# 02_Beam_Inputs.net
KiCad netlist of a schematic drawn in Altium Designer
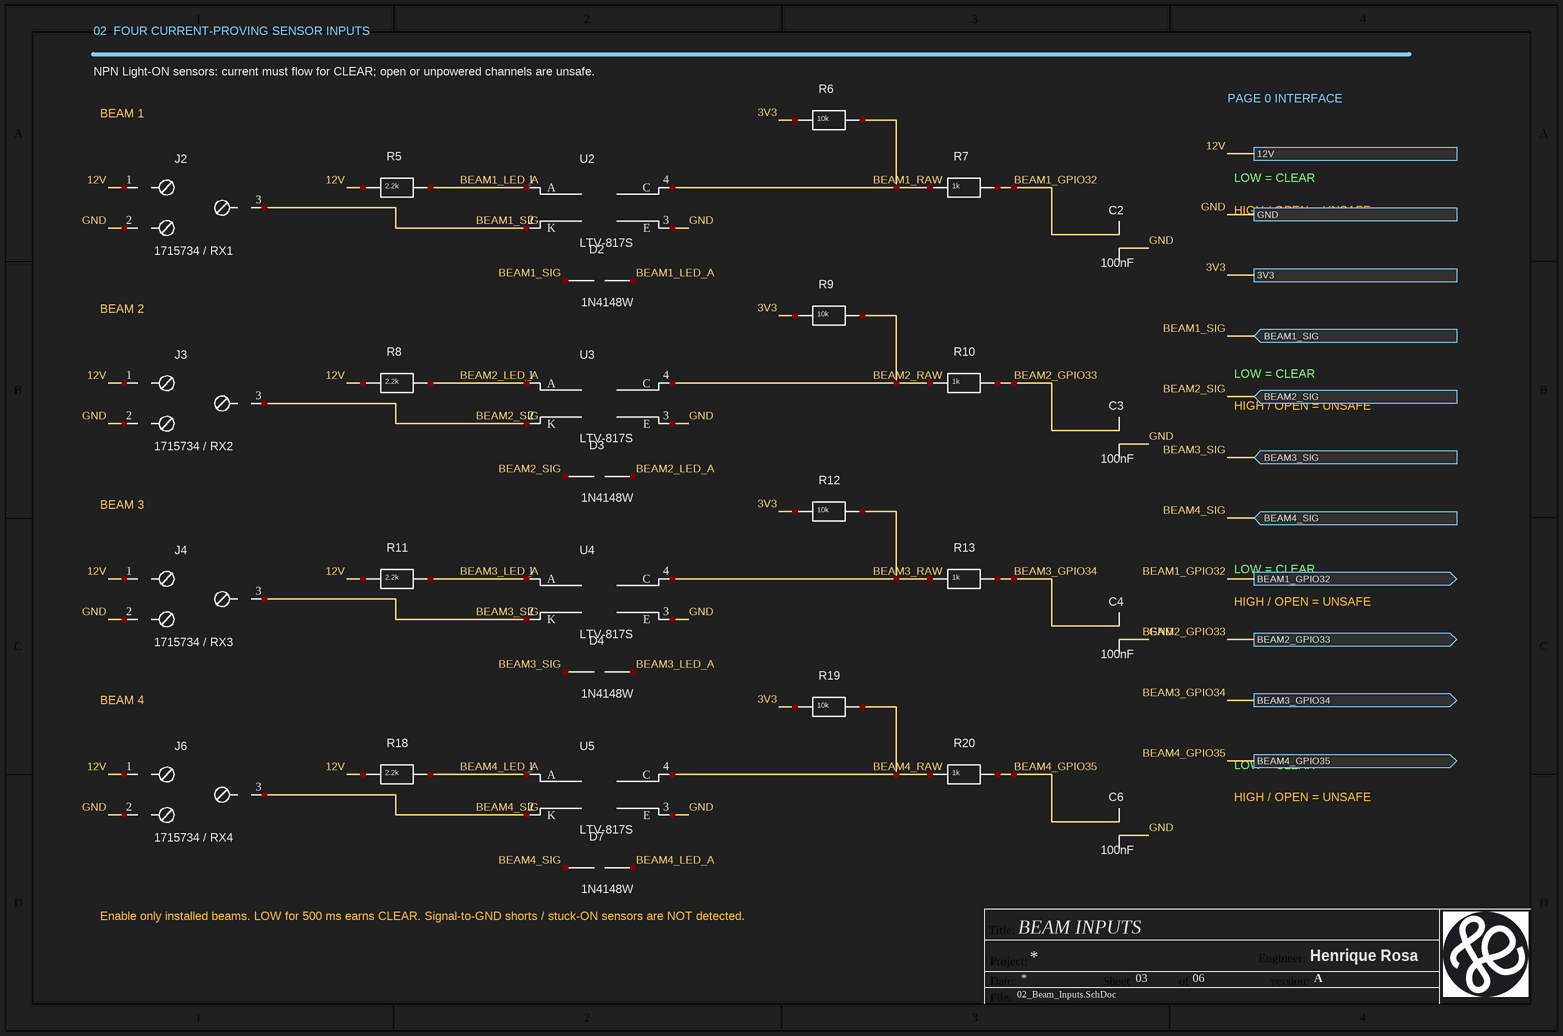
[diagram p0: 02_Beam_Inputs.SchDoc]

(export (version "E")
  (design (tool "Eeschema 10.0.6"))
  (components
    (comp (ref "C2")
      (value "100nF")
      (footprint "PCB - CAPACITOR - MLCC - MURATA GRM21B 0805_2012:MURATA GRM21B 0805_2012")
      (description "Input RC filter")
      (fields (field (name "PART NUMBER") "GRM21BR71H104KA01L") (field (name "MANUFACTURER") "Murata"))
      (libsource (lib "ReviewedComponents_20260912-233454") (part "GRM21BR71H104KA01L__C2_view"))
    )
    (comp (ref "C3")
      (value "100nF")
      (footprint "PCB - CAPACITOR - MLCC - MURATA GRM21B 0805_2012:MURATA GRM21B 0805_2012")
      (description "Input RC filter")
      (fields (field (name "PART NUMBER") "GRM21BR71H104KA01L") (field (name "MANUFACTURER") "Murata"))
      (libsource (lib "ReviewedComponents_20260912-233454") (part "GRM21BR71H104KA01L__C3_view"))
    )
    (comp (ref "C4")
      (value "100nF")
      (footprint "PCB - CAPACITOR - MLCC - MURATA GRM21B 0805_2012:MURATA GRM21B 0805_2012")
      (description "Input RC filter")
      (fields (field (name "PART NUMBER") "GRM21BR71H104KA01L") (field (name "MANUFACTURER") "Murata"))
      (libsource (lib "ReviewedComponents_20260912-233454") (part "GRM21BR71H104KA01L__C4_view"))
    )
    (comp (ref "C6")
      (value "100nF")
      (footprint "PCB - CAPACITOR - MLCC - MURATA GRM21B 0805_2012:MURATA GRM21B 0805_2012")
      (description "Input RC filter")
      (fields (field (name "PART NUMBER") "GRM21BR71H104KA01L") (field (name "MANUFACTURER") "Murata"))
      (libsource (lib "ReviewedComponents_20260912-233454") (part "GRM21BR71H104KA01L__C6_view"))
    )
    (comp (ref "D2")
      (value "1N4148W")
      (footprint "PinRepairFootprints:1N4148W_SOD123_A1_K2")
      (description "Reverse clamp: A to SIG; K to opto LED anode")
      (fields (field (name "MANUFACTURER") "Nexperia"))
      (libsource (lib "ReviewedComponents_20260912-233454") (part "1N4148W__D2_view"))
    )
    (comp (ref "D3")
      (value "1N4148W")
      (footprint "PinRepairFootprints:1N4148W_SOD123_A1_K2")
      (description "Reverse clamp: A to SIG; K to opto LED anode")
      (fields (field (name "MANUFACTURER") "Nexperia"))
      (libsource (lib "ReviewedComponents_20260912-233454") (part "1N4148W__D3_view"))
    )
    (comp (ref "D4")
      (value "1N4148W")
      (footprint "PinRepairFootprints:1N4148W_SOD123_A1_K2")
      (description "Reverse clamp: A to SIG; K to opto LED anode")
      (fields (field (name "MANUFACTURER") "Nexperia"))
      (libsource (lib "ReviewedComponents_20260912-233454") (part "1N4148W__D4_view"))
    )
    (comp (ref "D7")
      (value "1N4148W")
      (footprint "PinRepairFootprints:1N4148W_SOD123_A1_K2")
      (description "Reverse clamp: A to SIG; K to opto LED anode")
      (fields (field (name "MANUFACTURER") "Nexperia"))
      (libsource (lib "ReviewedComponents_20260912-233454") (part "1N4148W__D7_view"))
    )
    (comp (ref "J2")
      (value "1715734 / RX1")
      (footprint "OpticalHardware:PHOENIX_1715734_MKDS_3_508")
      (description "12V / GND / NPN signal terminal")
      (fields
        (field (name "MANUFACTURER") "Phoenix Contact")
        (field (name "MANUFACTURER PART NUMBER") "1715734")
      )
      (libsource (lib "ReviewedComponents_20260912-233454") (part "1715734__J2_view"))
    )
    (comp (ref "J3")
      (value "1715734 / RX2")
      (footprint "OpticalHardware:PHOENIX_1715734_MKDS_3_508")
      (description "12V / GND / NPN signal terminal")
      (fields
        (field (name "MANUFACTURER") "Phoenix Contact")
        (field (name "MANUFACTURER PART NUMBER") "1715734")
      )
      (libsource (lib "ReviewedComponents_20260912-233454") (part "1715734__J3_view"))
    )
    (comp (ref "J4")
      (value "1715734 / RX3")
      (footprint "OpticalHardware:PHOENIX_1715734_MKDS_3_508")
      (description "12V / GND / NPN signal terminal")
      (fields
        (field (name "MANUFACTURER") "Phoenix Contact")
        (field (name "MANUFACTURER PART NUMBER") "1715734")
      )
      (libsource (lib "ReviewedComponents_20260912-233454") (part "1715734__J4_view"))
    )
    (comp (ref "J6")
      (value "1715734 / RX4")
      (footprint "OpticalHardware:PHOENIX_1715734_MKDS_3_508")
      (description "12V / GND / NPN signal terminal")
      (fields
        (field (name "MANUFACTURER") "Phoenix Contact")
        (field (name "MANUFACTURER PART NUMBER") "1715734")
      )
      (libsource (lib "ReviewedComponents_20260912-233454") (part "1715734__J6_view"))
    )
    (comp (ref "R5")
      (value "2.2k")
      (footprint "PCB - RESISTOR - CHIP - YAGEO RES 0805_2012:YAGEO RES 0805_2012")
      (description "Optocoupler LED current limit")
      (fields (field (name "PART NUMBER") "RC0805FR-072K2L") (field (name "MANUFACTURER") "Yageo"))
      (libsource (lib "ReviewedComponents_20260912-233454") (part "RC0805FR-072K2L__R5_view"))
    )
    (comp (ref "R6")
      (value "10k")
      (footprint "PCB - RESISTOR - CHIP - YAGEO RES 0805_2012:YAGEO RES 0805_2012")
      (description "Pull-up earns unsafe if optocoupler is off")
      (fields (field (name "PART NUMBER") "RC0805FR-0710KL") (field (name "MANUFACTURER") "Yageo"))
      (libsource (lib "ReviewedComponents_20260912-233454") (part "RC0805FR-0710KL__R6_view"))
    )
    (comp (ref "R7")
      (value "1k")
      (footprint "PCB - RESISTOR - CHIP - YAGEO RES 0805_2012:YAGEO RES 0805_2012")
      (description "Input current limit")
      (fields (field (name "PART NUMBER") "RC0805FR-071KL") (field (name "MANUFACTURER") "Yageo"))
      (libsource (lib "ReviewedComponents_20260912-233454") (part "RC0805FR-071KL__R7_view"))
    )
    (comp (ref "R8")
      (value "2.2k")
      (footprint "PCB - RESISTOR - CHIP - YAGEO RES 0805_2012:YAGEO RES 0805_2012")
      (description "Optocoupler LED current limit")
      (fields (field (name "PART NUMBER") "RC0805FR-072K2L") (field (name "MANUFACTURER") "Yageo"))
      (libsource (lib "ReviewedComponents_20260912-233454") (part "RC0805FR-072K2L__R8_view"))
    )
    (comp (ref "R9")
      (value "10k")
      (footprint "PCB - RESISTOR - CHIP - YAGEO RES 0805_2012:YAGEO RES 0805_2012")
      (description "Pull-up earns unsafe if optocoupler is off")
      (fields (field (name "PART NUMBER") "RC0805FR-0710KL") (field (name "MANUFACTURER") "Yageo"))
      (libsource (lib "ReviewedComponents_20260912-233454") (part "RC0805FR-0710KL__R9_view"))
    )
    (comp (ref "R10")
      (value "1k")
      (footprint "PCB - RESISTOR - CHIP - YAGEO RES 0805_2012:YAGEO RES 0805_2012")
      (description "Input current limit")
      (fields (field (name "PART NUMBER") "RC0805FR-071KL") (field (name "MANUFACTURER") "Yageo"))
      (libsource (lib "ReviewedComponents_20260912-233454") (part "RC0805FR-071KL__R10_view"))
    )
    (comp (ref "R11")
      (value "2.2k")
      (footprint "PCB - RESISTOR - CHIP - YAGEO RES 0805_2012:YAGEO RES 0805_2012")
      (description "Optocoupler LED current limit")
      (fields (field (name "PART NUMBER") "RC0805FR-072K2L") (field (name "MANUFACTURER") "Yageo"))
      (libsource (lib "ReviewedComponents_20260912-233454") (part "RC0805FR-072K2L__R11_view"))
    )
    (comp (ref "R12")
      (value "10k")
      (footprint "PCB - RESISTOR - CHIP - YAGEO RES 0805_2012:YAGEO RES 0805_2012")
      (description "Pull-up earns unsafe if optocoupler is off")
      (fields (field (name "PART NUMBER") "RC0805FR-0710KL") (field (name "MANUFACTURER") "Yageo"))
      (libsource (lib "ReviewedComponents_20260912-233454") (part "RC0805FR-0710KL__R12_view"))
    )
    (comp (ref "R13")
      (value "1k")
      (footprint "PCB - RESISTOR - CHIP - YAGEO RES 0805_2012:YAGEO RES 0805_2012")
      (description "Input current limit")
      (fields (field (name "PART NUMBER") "RC0805FR-071KL") (field (name "MANUFACTURER") "Yageo"))
      (libsource (lib "ReviewedComponents_20260912-233454") (part "RC0805FR-071KL__R13_view"))
    )
    (comp (ref "R18")
      (value "2.2k")
      (footprint "PCB - RESISTOR - CHIP - YAGEO RES 0805_2012:YAGEO RES 0805_2012")
      (description "Optocoupler LED current limit")
      (fields (field (name "PART NUMBER") "RC0805FR-072K2L") (field (name "MANUFACTURER") "Yageo"))
      (libsource (lib "ReviewedComponents_20260912-233454") (part "RC0805FR-072K2L__R18_view"))
    )
    (comp (ref "R19")
      (value "10k")
      (footprint "PCB - RESISTOR - CHIP - YAGEO RES 0805_2012:YAGEO RES 0805_2012")
      (description "Pull-up earns unsafe if optocoupler is off")
      (fields (field (name "PART NUMBER") "RC0805FR-0710KL") (field (name "MANUFACTURER") "Yageo"))
      (libsource (lib "ReviewedComponents_20260912-233454") (part "RC0805FR-0710KL__R19_view"))
    )
    (comp (ref "R20")
      (value "1k")
      (footprint "PCB - RESISTOR - CHIP - YAGEO RES 0805_2012:YAGEO RES 0805_2012")
      (description "Input current limit")
      (fields (field (name "PART NUMBER") "RC0805FR-071KL") (field (name "MANUFACTURER") "Yageo"))
      (libsource (lib "ReviewedComponents_20260912-233454") (part "RC0805FR-071KL__R20_view"))
    )
    (comp (ref "U2")
      (value "LTV-817S")
      (footprint "PCB - OPTOISOLATOR - LITEON LTV-817:LITEON LTV-817")
      (description "Phototransistor optocoupler")
      (fields
        (field (name "MANUFACTURER") "Lite-On")
        (field (name "MANUFACTURER PART NUMBER") "LTV-817S-TA1")
      )
      (libsource (lib "ReviewedComponents_20260912-233454") (part "LTV-817S-TA1__U2_view"))
    )
    (comp (ref "U3")
      (value "LTV-817S")
      (footprint "PCB - OPTOISOLATOR - LITEON LTV-817:LITEON LTV-817")
      (description "Phototransistor optocoupler")
      (fields
        (field (name "MANUFACTURER") "Lite-On")
        (field (name "MANUFACTURER PART NUMBER") "LTV-817S-TA1")
      )
      (libsource (lib "ReviewedComponents_20260912-233454") (part "LTV-817S-TA1__U3_view"))
    )
    (comp (ref "U4")
      (value "LTV-817S")
      (footprint "PCB - OPTOISOLATOR - LITEON LTV-817:LITEON LTV-817")
      (description "Phototransistor optocoupler")
      (fields
        (field (name "MANUFACTURER") "Lite-On")
        (field (name "MANUFACTURER PART NUMBER") "LTV-817S-TA1")
      )
      (libsource (lib "ReviewedComponents_20260912-233454") (part "LTV-817S-TA1__U4_view"))
    )
    (comp (ref "U5")
      (value "LTV-817S")
      (footprint "PCB - OPTOISOLATOR - LITEON LTV-817:LITEON LTV-817")
      (description "Phototransistor optocoupler")
      (fields
        (field (name "MANUFACTURER") "Lite-On")
        (field (name "MANUFACTURER PART NUMBER") "LTV-817S-TA1")
      )
      (libsource (lib "ReviewedComponents_20260912-233454") (part "LTV-817S-TA1__U5_view"))
    )
  )
  (nets
    (net (code "1") (name "/3V3") (class "Default")
      (node (ref "R12") (pin "1") (pinfunction "1_1") (pintype "passive"))
      (node (ref "R19") (pin "1") (pinfunction "1_1") (pintype "passive"))
      (node (ref "R6") (pin "1") (pinfunction "1_1") (pintype "passive"))
      (node (ref "R9") (pin "1") (pinfunction "1_1") (pintype "passive"))
    )
    (net (code "2") (name "/12V") (class "Default")
      (node (ref "J2") (pin "1") (pinfunction "+12V_1") (pintype "passive"))
      (node (ref "J3") (pin "1") (pinfunction "+12V_1") (pintype "passive"))
      (node (ref "J4") (pin "1") (pinfunction "+12V_1") (pintype "passive"))
      (node (ref "J6") (pin "1") (pinfunction "+12V_1") (pintype "passive"))
      (node (ref "R11") (pin "1") (pinfunction "1_1") (pintype "passive"))
      (node (ref "R18") (pin "1") (pinfunction "1_1") (pintype "passive"))
      (node (ref "R5") (pin "1") (pinfunction "1_1") (pintype "passive"))
      (node (ref "R8") (pin "1") (pinfunction "1_1") (pintype "passive"))
    )
    (net (code "3") (name "/BEAM1_GPIO32") (class "Default")
      (node (ref "R7") (pin "2") (pinfunction "2_2") (pintype "passive"))
    )
    (net (code "4") (name "/BEAM1_LED_A") (class "Default")
      (node (ref "D2") (pin "2") (pinfunction "K_2") (pintype "passive"))
      (node (ref "R5") (pin "2") (pinfunction "2_2") (pintype "passive"))
      (node (ref "U2") (pin "1") (pinfunction "A_1") (pintype "passive"))
    )
    (net (code "5") (name "/BEAM1_RAW") (class "Default")
      (node (ref "R6") (pin "2") (pinfunction "2_2") (pintype "passive"))
      (node (ref "R7") (pin "1") (pinfunction "1_1") (pintype "passive"))
      (node (ref "U2") (pin "4") (pinfunction "C_4") (pintype "open_collector"))
    )
    (net (code "6") (name "/BEAM1_SIG") (class "Default")
      (node (ref "D2") (pin "1") (pinfunction "A_1") (pintype "passive"))
      (node (ref "J2") (pin "3") (pinfunction "OUT_3") (pintype "passive"))
      (node (ref "U2") (pin "2") (pinfunction "K_2") (pintype "passive"))
    )
    (net (code "7") (name "/BEAM2_GPIO33") (class "Default")
      (node (ref "R10") (pin "2") (pinfunction "2_2") (pintype "passive"))
    )
    (net (code "8") (name "/BEAM2_LED_A") (class "Default")
      (node (ref "D3") (pin "2") (pinfunction "K_2") (pintype "passive"))
      (node (ref "R8") (pin "2") (pinfunction "2_2") (pintype "passive"))
      (node (ref "U3") (pin "1") (pinfunction "A_1") (pintype "passive"))
    )
    (net (code "9") (name "/BEAM2_RAW") (class "Default")
      (node (ref "R10") (pin "1") (pinfunction "1_1") (pintype "passive"))
      (node (ref "R9") (pin "2") (pinfunction "2_2") (pintype "passive"))
      (node (ref "U3") (pin "4") (pinfunction "C_4") (pintype "open_collector"))
    )
    (net (code "10") (name "/BEAM2_SIG") (class "Default")
      (node (ref "D3") (pin "1") (pinfunction "A_1") (pintype "passive"))
      (node (ref "J3") (pin "3") (pinfunction "OUT_3") (pintype "passive"))
      (node (ref "U3") (pin "2") (pinfunction "K_2") (pintype "passive"))
    )
    (net (code "11") (name "/BEAM3_GPIO34") (class "Default")
      (node (ref "R13") (pin "2") (pinfunction "2_2") (pintype "passive"))
    )
    (net (code "12") (name "/BEAM3_LED_A") (class "Default")
      (node (ref "D4") (pin "2") (pinfunction "K_2") (pintype "passive"))
      (node (ref "R11") (pin "2") (pinfunction "2_2") (pintype "passive"))
      (node (ref "U4") (pin "1") (pinfunction "A_1") (pintype "passive"))
    )
    (net (code "13") (name "/BEAM3_RAW") (class "Default")
      (node (ref "R12") (pin "2") (pinfunction "2_2") (pintype "passive"))
      (node (ref "R13") (pin "1") (pinfunction "1_1") (pintype "passive"))
      (node (ref "U4") (pin "4") (pinfunction "C_4") (pintype "open_collector"))
    )
    (net (code "14") (name "/BEAM3_SIG") (class "Default")
      (node (ref "D4") (pin "1") (pinfunction "A_1") (pintype "passive"))
      (node (ref "J4") (pin "3") (pinfunction "OUT_3") (pintype "passive"))
      (node (ref "U4") (pin "2") (pinfunction "K_2") (pintype "passive"))
    )
    (net (code "15") (name "/BEAM4_GPIO35") (class "Default")
      (node (ref "R20") (pin "2") (pinfunction "2_2") (pintype "passive"))
    )
    (net (code "16") (name "/BEAM4_LED_A") (class "Default")
      (node (ref "D7") (pin "2") (pinfunction "K_2") (pintype "passive"))
      (node (ref "R18") (pin "2") (pinfunction "2_2") (pintype "passive"))
      (node (ref "U5") (pin "1") (pinfunction "A_1") (pintype "passive"))
    )
    (net (code "17") (name "/BEAM4_RAW") (class "Default")
      (node (ref "R19") (pin "2") (pinfunction "2_2") (pintype "passive"))
      (node (ref "R20") (pin "1") (pinfunction "1_1") (pintype "passive"))
      (node (ref "U5") (pin "4") (pinfunction "C_4") (pintype "open_collector"))
    )
    (net (code "18") (name "/BEAM4_SIG") (class "Default")
      (node (ref "D7") (pin "1") (pinfunction "A_1") (pintype "passive"))
      (node (ref "J6") (pin "3") (pinfunction "OUT_3") (pintype "passive"))
      (node (ref "U5") (pin "2") (pinfunction "K_2") (pintype "passive"))
    )
    (net (code "19") (name "/GND") (class "Default")
      (node (ref "J2") (pin "2") (pinfunction "0V_2") (pintype "passive"))
      (node (ref "J3") (pin "2") (pinfunction "0V_2") (pintype "passive"))
      (node (ref "J4") (pin "2") (pinfunction "0V_2") (pintype "passive"))
      (node (ref "J6") (pin "2") (pinfunction "0V_2") (pintype "passive"))
      (node (ref "U2") (pin "3") (pinfunction "E_3") (pintype "passive"))
      (node (ref "U3") (pin "3") (pinfunction "E_3") (pintype "passive"))
      (node (ref "U4") (pin "3") (pinfunction "E_3") (pintype "passive"))
      (node (ref "U5") (pin "3") (pinfunction "E_3") (pintype "passive"))
    )
    (net (code "20") (name "unconnected-(C2-Pad1)") (class "Default")
      (node (ref "C2") (pin "1") (pinfunction "1_1") (pintype "passive"))
    )
    (net (code "21") (name "unconnected-(C2-Pad2)") (class "Default")
      (node (ref "C2") (pin "2") (pinfunction "2_2") (pintype "passive"))
    )
    (net (code "22") (name "unconnected-(C3-Pad1)") (class "Default")
      (node (ref "C3") (pin "1") (pinfunction "1_1") (pintype "passive"))
    )
    (net (code "23") (name "unconnected-(C3-Pad2)") (class "Default")
      (node (ref "C3") (pin "2") (pinfunction "2_2") (pintype "passive"))
    )
    (net (code "24") (name "unconnected-(C4-Pad1)") (class "Default")
      (node (ref "C4") (pin "1") (pinfunction "1_1") (pintype "passive"))
    )
    (net (code "25") (name "unconnected-(C4-Pad2)") (class "Default")
      (node (ref "C4") (pin "2") (pinfunction "2_2") (pintype "passive"))
    )
    (net (code "26") (name "unconnected-(C6-Pad1)") (class "Default")
      (node (ref "C6") (pin "1") (pinfunction "1_1") (pintype "passive"))
    )
    (net (code "27") (name "unconnected-(C6-Pad2)") (class "Default")
      (node (ref "C6") (pin "2") (pinfunction "2_2") (pintype "passive"))
    )
  )
)
